# Debug_Board_-_Rev_A.net
KiCad netlist of a schematic drawn in EAGLE
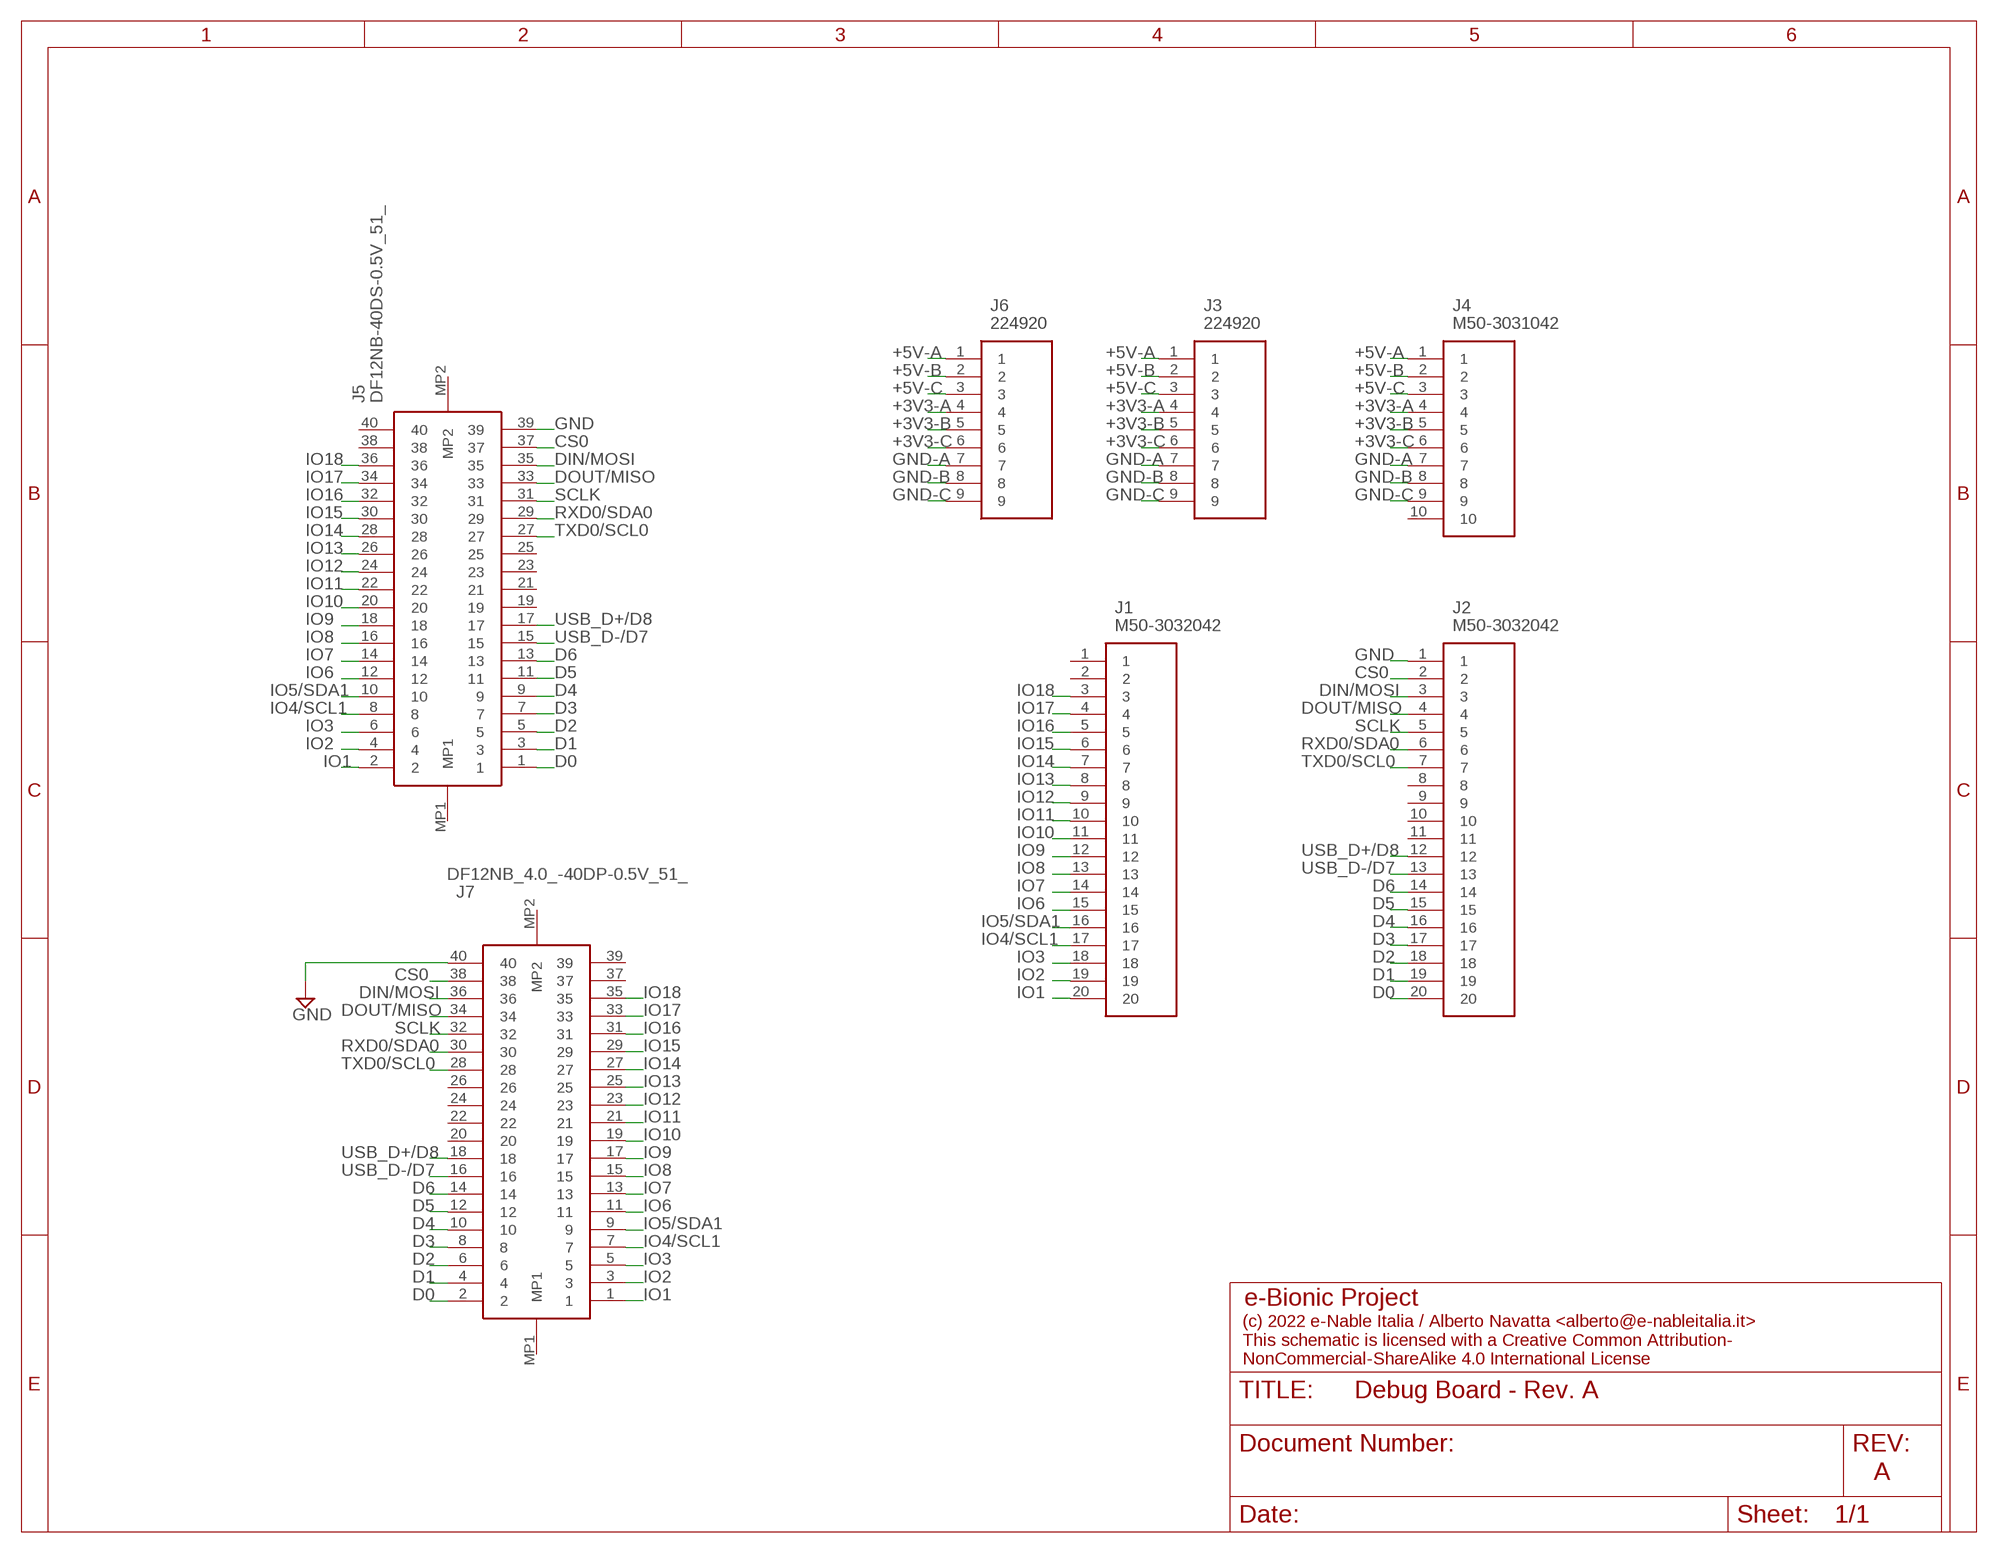
[diagram p0: schematic, sheet 1]

(export (version "E")
  (design (tool "Eeschema 10.0.6"))
  (components
    (comp (ref "J1")
      (value "M50-3032042")
      (footprint "eagle-import:M503032042")
      (fields (field (name "MOUSER_PART_NUMBER") "855-M50-3032042"))
      (libsource (lib "eagle-import") (part "M50-3032042"))
    )
    (comp (ref "J2")
      (value "M50-3032042")
      (footprint "eagle-import:M503032042")
      (fields (field (name "MOUSER_PART_NUMBER") "855-M50-3032042"))
      (libsource (lib "eagle-import") (part "M50-3032042"))
    )
    (comp (ref "J3")
      (value "224920")
      (footprint "eagle-import:224920")
      (fields (field (name "MOUSER_PART_NUMBER") "305-224920"))
      (libsource (lib "eagle-import") (part "224920"))
    )
    (comp (ref "J4")
      (value "M50-3031042")
      (footprint "eagle-import:M503031042")
      (fields (field (name "MOUSER_PART_NUMBER") "855-M50-3031042"))
      (libsource (lib "eagle-import") (part "M50-3031042"))
    )
    (comp (ref "J5")
      (value "DF12NB-40DS-0.5V_51_")
      (footprint "eagle-import:DF12NB40DS05V51")
      (fields
        (field (name "MANUFACTURER_PART_NUMBER") "DF12NB-40DS-0.5V(51)")
        (field (name "MOUSER_PART_NUMBER") "798-DF12NB40DS0551")
      )
      (libsource (lib "eagle-import") (part "DF12NB-40DS-0.5V_51_"))
    )
    (comp (ref "J6")
      (value "224920")
      (footprint "eagle-import:224920")
      (fields (field (name "MOUSER_PART_NUMBER") "305-224920"))
      (libsource (lib "eagle-import") (part "224920"))
    )
    (comp (ref "J7")
      (value "DF12NB_4.0_-40DP-0.5V_51_")
      (footprint "eagle-import:DF12NB4040DP05V51")
      (fields
        (field (name "MANUFACTURER_PART_NUMBER") "DF12NB(4.0)-40DP-0.5V(51)")
        (field (name "MOUSER_PART_NUMBER") "798-DF12NB4040DP0551")
      )
      (libsource (lib "eagle-import") (part "DF12NB_4.0_-40DP-0.5V_51_"))
    )
  )
  (nets
    (net (code "1") (name "/+3V3-A") (class "Default")
      (node (ref "J3") (pin "4") (pinfunction "4_4") (pintype "bidirectional"))
      (node (ref "J4") (pin "4") (pinfunction "4_4") (pintype "bidirectional"))
      (node (ref "J6") (pin "4") (pinfunction "4_4") (pintype "bidirectional"))
    )
    (net (code "2") (name "/+3V3-B") (class "Default")
      (node (ref "J3") (pin "5") (pinfunction "5_5") (pintype "bidirectional"))
      (node (ref "J4") (pin "5") (pinfunction "5_5") (pintype "bidirectional"))
      (node (ref "J6") (pin "5") (pinfunction "5_5") (pintype "bidirectional"))
    )
    (net (code "3") (name "/+3V3-C") (class "Default")
      (node (ref "J3") (pin "6") (pinfunction "6_6") (pintype "bidirectional"))
      (node (ref "J4") (pin "6") (pinfunction "6_6") (pintype "bidirectional"))
      (node (ref "J6") (pin "6") (pinfunction "6_6") (pintype "bidirectional"))
    )
    (net (code "4") (name "/+5V-A") (class "Default")
      (node (ref "J3") (pin "1") (pinfunction "1_1") (pintype "bidirectional"))
      (node (ref "J4") (pin "1") (pinfunction "1_1") (pintype "bidirectional"))
      (node (ref "J6") (pin "1") (pinfunction "1_1") (pintype "bidirectional"))
    )
    (net (code "5") (name "/+5V-B") (class "Default")
      (node (ref "J3") (pin "2") (pinfunction "2_2") (pintype "bidirectional"))
      (node (ref "J4") (pin "2") (pinfunction "2_2") (pintype "bidirectional"))
      (node (ref "J6") (pin "2") (pinfunction "2_2") (pintype "bidirectional"))
    )
    (net (code "6") (name "/+5V-C") (class "Default")
      (node (ref "J3") (pin "3") (pinfunction "3_3") (pintype "bidirectional"))
      (node (ref "J4") (pin "3") (pinfunction "3_3") (pintype "bidirectional"))
      (node (ref "J6") (pin "3") (pinfunction "3_3") (pintype "bidirectional"))
    )
    (net (code "7") (name "/CS0") (class "Default")
      (node (ref "J2") (pin "2") (pinfunction "2_2") (pintype "bidirectional"))
      (node (ref "J5") (pin "37") (pinfunction "37_37") (pintype "bidirectional"))
      (node (ref "J7") (pin "38") (pinfunction "38_38") (pintype "bidirectional"))
    )
    (net (code "8") (name "/D0") (class "Default")
      (node (ref "J2") (pin "20") (pinfunction "20_20") (pintype "bidirectional"))
      (node (ref "J5") (pin "1") (pinfunction "1_1") (pintype "bidirectional"))
      (node (ref "J7") (pin "2") (pinfunction "2_2") (pintype "bidirectional"))
    )
    (net (code "9") (name "/D1") (class "Default")
      (node (ref "J2") (pin "19") (pinfunction "19_19") (pintype "bidirectional"))
      (node (ref "J5") (pin "3") (pinfunction "3_3") (pintype "bidirectional"))
      (node (ref "J7") (pin "4") (pinfunction "4_4") (pintype "bidirectional"))
    )
    (net (code "10") (name "/D2") (class "Default")
      (node (ref "J2") (pin "18") (pinfunction "18_18") (pintype "bidirectional"))
      (node (ref "J5") (pin "5") (pinfunction "5_5") (pintype "bidirectional"))
      (node (ref "J7") (pin "6") (pinfunction "6_6") (pintype "bidirectional"))
    )
    (net (code "11") (name "/D3") (class "Default")
      (node (ref "J2") (pin "17") (pinfunction "17_17") (pintype "bidirectional"))
      (node (ref "J5") (pin "7") (pinfunction "7_7") (pintype "bidirectional"))
      (node (ref "J7") (pin "8") (pinfunction "8_8") (pintype "bidirectional"))
    )
    (net (code "12") (name "/D4") (class "Default")
      (node (ref "J2") (pin "16") (pinfunction "16_16") (pintype "bidirectional"))
      (node (ref "J5") (pin "9") (pinfunction "9_9") (pintype "bidirectional"))
      (node (ref "J7") (pin "10") (pinfunction "10_10") (pintype "bidirectional"))
    )
    (net (code "13") (name "/D5") (class "Default")
      (node (ref "J2") (pin "15") (pinfunction "15_15") (pintype "bidirectional"))
      (node (ref "J5") (pin "11") (pinfunction "11_11") (pintype "bidirectional"))
      (node (ref "J7") (pin "12") (pinfunction "12_12") (pintype "bidirectional"))
    )
    (net (code "14") (name "/D6") (class "Default")
      (node (ref "J2") (pin "14") (pinfunction "14_14") (pintype "bidirectional"))
      (node (ref "J5") (pin "13") (pinfunction "13_13") (pintype "bidirectional"))
      (node (ref "J7") (pin "14") (pinfunction "14_14") (pintype "bidirectional"))
    )
    (net (code "15") (name "/DIN{slash}MOSI") (class "Default")
      (node (ref "J2") (pin "3") (pinfunction "3_3") (pintype "bidirectional"))
      (node (ref "J5") (pin "35") (pinfunction "35_35") (pintype "bidirectional"))
      (node (ref "J7") (pin "36") (pinfunction "36_36") (pintype "bidirectional"))
    )
    (net (code "16") (name "/DOUT{slash}MISO") (class "Default")
      (node (ref "J2") (pin "4") (pinfunction "4_4") (pintype "bidirectional"))
      (node (ref "J5") (pin "33") (pinfunction "33_33") (pintype "bidirectional"))
      (node (ref "J7") (pin "34") (pinfunction "34_34") (pintype "bidirectional"))
    )
    (net (code "17") (name "/GND-A") (class "Default")
      (node (ref "J3") (pin "7") (pinfunction "7_7") (pintype "bidirectional"))
      (node (ref "J4") (pin "7") (pinfunction "7_7") (pintype "bidirectional"))
      (node (ref "J6") (pin "7") (pinfunction "7_7") (pintype "bidirectional"))
    )
    (net (code "18") (name "/GND-B") (class "Default")
      (node (ref "J3") (pin "8") (pinfunction "8_8") (pintype "bidirectional"))
      (node (ref "J4") (pin "8") (pinfunction "8_8") (pintype "bidirectional"))
      (node (ref "J6") (pin "8") (pinfunction "8_8") (pintype "bidirectional"))
    )
    (net (code "19") (name "/GND-C") (class "Default")
      (node (ref "J3") (pin "9") (pinfunction "9_9") (pintype "bidirectional"))
      (node (ref "J4") (pin "9") (pinfunction "9_9") (pintype "bidirectional"))
      (node (ref "J6") (pin "9") (pinfunction "9_9") (pintype "bidirectional"))
    )
    (net (code "20") (name "/IO1") (class "Default")
      (node (ref "J1") (pin "20") (pinfunction "20_20") (pintype "bidirectional"))
      (node (ref "J5") (pin "2") (pinfunction "2_2") (pintype "bidirectional"))
      (node (ref "J7") (pin "1") (pinfunction "1_1") (pintype "bidirectional"))
    )
    (net (code "21") (name "/IO2") (class "Default")
      (node (ref "J1") (pin "19") (pinfunction "19_19") (pintype "bidirectional"))
      (node (ref "J5") (pin "4") (pinfunction "4_4") (pintype "bidirectional"))
      (node (ref "J7") (pin "3") (pinfunction "3_3") (pintype "bidirectional"))
    )
    (net (code "22") (name "/IO3") (class "Default")
      (node (ref "J1") (pin "18") (pinfunction "18_18") (pintype "bidirectional"))
      (node (ref "J5") (pin "6") (pinfunction "6_6") (pintype "bidirectional"))
      (node (ref "J7") (pin "5") (pinfunction "5_5") (pintype "bidirectional"))
    )
    (net (code "23") (name "/IO4{slash}SCL1") (class "Default")
      (node (ref "J1") (pin "17") (pinfunction "17_17") (pintype "bidirectional"))
      (node (ref "J5") (pin "8") (pinfunction "8_8") (pintype "bidirectional"))
      (node (ref "J7") (pin "7") (pinfunction "7_7") (pintype "bidirectional"))
    )
    (net (code "24") (name "/IO5{slash}SDA1") (class "Default")
      (node (ref "J1") (pin "16") (pinfunction "16_16") (pintype "bidirectional"))
      (node (ref "J5") (pin "10") (pinfunction "10_10") (pintype "bidirectional"))
      (node (ref "J7") (pin "9") (pinfunction "9_9") (pintype "bidirectional"))
    )
    (net (code "25") (name "/IO6") (class "Default")
      (node (ref "J1") (pin "15") (pinfunction "15_15") (pintype "bidirectional"))
      (node (ref "J5") (pin "12") (pinfunction "12_12") (pintype "bidirectional"))
      (node (ref "J7") (pin "11") (pinfunction "11_11") (pintype "bidirectional"))
    )
    (net (code "26") (name "/IO7") (class "Default")
      (node (ref "J1") (pin "14") (pinfunction "14_14") (pintype "bidirectional"))
      (node (ref "J5") (pin "14") (pinfunction "14_14") (pintype "bidirectional"))
      (node (ref "J7") (pin "13") (pinfunction "13_13") (pintype "bidirectional"))
    )
    (net (code "27") (name "/IO8") (class "Default")
      (node (ref "J1") (pin "13") (pinfunction "13_13") (pintype "bidirectional"))
      (node (ref "J5") (pin "16") (pinfunction "16_16") (pintype "bidirectional"))
      (node (ref "J7") (pin "15") (pinfunction "15_15") (pintype "bidirectional"))
    )
    (net (code "28") (name "/IO9") (class "Default")
      (node (ref "J1") (pin "12") (pinfunction "12_12") (pintype "bidirectional"))
      (node (ref "J5") (pin "18") (pinfunction "18_18") (pintype "bidirectional"))
      (node (ref "J7") (pin "17") (pinfunction "17_17") (pintype "bidirectional"))
    )
    (net (code "29") (name "/IO10") (class "Default")
      (node (ref "J1") (pin "11") (pinfunction "11_11") (pintype "bidirectional"))
      (node (ref "J5") (pin "20") (pinfunction "20_20") (pintype "bidirectional"))
      (node (ref "J7") (pin "19") (pinfunction "19_19") (pintype "bidirectional"))
    )
    (net (code "30") (name "/IO11") (class "Default")
      (node (ref "J1") (pin "10") (pinfunction "10_10") (pintype "bidirectional"))
      (node (ref "J5") (pin "22") (pinfunction "22_22") (pintype "bidirectional"))
      (node (ref "J7") (pin "21") (pinfunction "21_21") (pintype "bidirectional"))
    )
    (net (code "31") (name "/IO12") (class "Default")
      (node (ref "J1") (pin "9") (pinfunction "9_9") (pintype "bidirectional"))
      (node (ref "J5") (pin "24") (pinfunction "24_24") (pintype "bidirectional"))
      (node (ref "J7") (pin "23") (pinfunction "23_23") (pintype "bidirectional"))
    )
    (net (code "32") (name "/IO13") (class "Default")
      (node (ref "J1") (pin "8") (pinfunction "8_8") (pintype "bidirectional"))
      (node (ref "J5") (pin "26") (pinfunction "26_26") (pintype "bidirectional"))
      (node (ref "J7") (pin "25") (pinfunction "25_25") (pintype "bidirectional"))
    )
    (net (code "33") (name "/IO14") (class "Default")
      (node (ref "J1") (pin "7") (pinfunction "7_7") (pintype "bidirectional"))
      (node (ref "J5") (pin "28") (pinfunction "28_28") (pintype "bidirectional"))
      (node (ref "J7") (pin "27") (pinfunction "27_27") (pintype "bidirectional"))
    )
    (net (code "34") (name "/IO15") (class "Default")
      (node (ref "J1") (pin "6") (pinfunction "6_6") (pintype "bidirectional"))
      (node (ref "J5") (pin "30") (pinfunction "30_30") (pintype "bidirectional"))
      (node (ref "J7") (pin "29") (pinfunction "29_29") (pintype "bidirectional"))
    )
    (net (code "35") (name "/IO16") (class "Default")
      (node (ref "J1") (pin "5") (pinfunction "5_5") (pintype "bidirectional"))
      (node (ref "J5") (pin "32") (pinfunction "32_32") (pintype "bidirectional"))
      (node (ref "J7") (pin "31") (pinfunction "31_31") (pintype "bidirectional"))
    )
    (net (code "36") (name "/IO17") (class "Default")
      (node (ref "J1") (pin "4") (pinfunction "4_4") (pintype "bidirectional"))
      (node (ref "J5") (pin "34") (pinfunction "34_34") (pintype "bidirectional"))
      (node (ref "J7") (pin "33") (pinfunction "33_33") (pintype "bidirectional"))
    )
    (net (code "37") (name "/IO18") (class "Default")
      (node (ref "J1") (pin "3") (pinfunction "3_3") (pintype "bidirectional"))
      (node (ref "J5") (pin "36") (pinfunction "36_36") (pintype "bidirectional"))
      (node (ref "J7") (pin "35") (pinfunction "35_35") (pintype "bidirectional"))
    )
    (net (code "38") (name "/RXD0{slash}SDA0") (class "Default")
      (node (ref "J2") (pin "6") (pinfunction "6_6") (pintype "bidirectional"))
      (node (ref "J5") (pin "29") (pinfunction "29_29") (pintype "bidirectional"))
      (node (ref "J7") (pin "30") (pinfunction "30_30") (pintype "bidirectional"))
    )
    (net (code "39") (name "/SCLK") (class "Default")
      (node (ref "J2") (pin "5") (pinfunction "5_5") (pintype "bidirectional"))
      (node (ref "J5") (pin "31") (pinfunction "31_31") (pintype "bidirectional"))
      (node (ref "J7") (pin "32") (pinfunction "32_32") (pintype "bidirectional"))
    )
    (net (code "40") (name "/TXD0{slash}SCL0") (class "Default")
      (node (ref "J2") (pin "7") (pinfunction "7_7") (pintype "bidirectional"))
      (node (ref "J5") (pin "27") (pinfunction "27_27") (pintype "bidirectional"))
      (node (ref "J7") (pin "28") (pinfunction "28_28") (pintype "bidirectional"))
    )
    (net (code "41") (name "/USB_D+{slash}D8") (class "Default")
      (node (ref "J2") (pin "12") (pinfunction "12_12") (pintype "bidirectional"))
      (node (ref "J5") (pin "17") (pinfunction "17_17") (pintype "bidirectional"))
      (node (ref "J7") (pin "18") (pinfunction "18_18") (pintype "bidirectional"))
    )
    (net (code "42") (name "/USB_D-{slash}D7") (class "Default")
      (node (ref "J2") (pin "13") (pinfunction "13_13") (pintype "bidirectional"))
      (node (ref "J5") (pin "15") (pinfunction "15_15") (pintype "bidirectional"))
      (node (ref "J7") (pin "16") (pinfunction "16_16") (pintype "bidirectional"))
    )
    (net (code "43") (name "GND") (class "Default")
      (node (ref "J2") (pin "1") (pinfunction "1_1") (pintype "bidirectional"))
      (node (ref "J5") (pin "39") (pinfunction "39_39") (pintype "bidirectional"))
      (node (ref "J7") (pin "40") (pinfunction "40_40") (pintype "bidirectional"))
    )
    (net (code "44") (name "unconnected-(J1-Pad1)") (class "Default")
      (node (ref "J1") (pin "1") (pinfunction "1_1") (pintype "bidirectional"))
    )
    (net (code "45") (name "unconnected-(J1-Pad2)") (class "Default")
      (node (ref "J1") (pin "2") (pinfunction "2_2") (pintype "bidirectional"))
    )
    (net (code "46") (name "unconnected-(J2-Pad8)") (class "Default")
      (node (ref "J2") (pin "8") (pinfunction "8_8") (pintype "bidirectional"))
    )
    (net (code "47") (name "unconnected-(J2-Pad9)") (class "Default")
      (node (ref "J2") (pin "9") (pinfunction "9_9") (pintype "bidirectional"))
    )
    (net (code "48") (name "unconnected-(J2-Pad10)") (class "Default")
      (node (ref "J2") (pin "10") (pinfunction "10_10") (pintype "bidirectional"))
    )
    (net (code "49") (name "unconnected-(J2-Pad11)") (class "Default")
      (node (ref "J2") (pin "11") (pinfunction "11_11") (pintype "bidirectional"))
    )
    (net (code "50") (name "unconnected-(J4-Pad10)") (class "Default")
      (node (ref "J4") (pin "10") (pinfunction "10_10") (pintype "bidirectional"))
    )
    (net (code "51") (name "unconnected-(J5-Pad19)") (class "Default")
      (node (ref "J5") (pin "19") (pinfunction "19_19") (pintype "bidirectional"))
    )
    (net (code "52") (name "unconnected-(J5-Pad21)") (class "Default")
      (node (ref "J5") (pin "21") (pinfunction "21_21") (pintype "bidirectional"))
    )
    (net (code "53") (name "unconnected-(J5-Pad23)") (class "Default")
      (node (ref "J5") (pin "23") (pinfunction "23_23") (pintype "bidirectional"))
    )
    (net (code "54") (name "unconnected-(J5-Pad25)") (class "Default")
      (node (ref "J5") (pin "25") (pinfunction "25_25") (pintype "bidirectional"))
    )
    (net (code "55") (name "unconnected-(J5-Pad38)") (class "Default")
      (node (ref "J5") (pin "38") (pinfunction "38_38") (pintype "bidirectional"))
    )
    (net (code "56") (name "unconnected-(J5-Pad40)") (class "Default")
      (node (ref "J5") (pin "40") (pinfunction "40_40") (pintype "bidirectional"))
    )
    (net (code "57") (name "unconnected-(J5-PadMP1)") (class "Default")
      (node (ref "J5") (pin "MP1") (pinfunction "MP1_MP1") (pintype "bidirectional"))
    )
    (net (code "58") (name "unconnected-(J5-PadMP2)") (class "Default")
      (node (ref "J5") (pin "MP2") (pinfunction "MP2_MP2") (pintype "bidirectional"))
    )
    (net (code "59") (name "unconnected-(J7-Pad20)") (class "Default")
      (node (ref "J7") (pin "20") (pinfunction "20_20") (pintype "bidirectional"))
    )
    (net (code "60") (name "unconnected-(J7-Pad22)") (class "Default")
      (node (ref "J7") (pin "22") (pinfunction "22_22") (pintype "bidirectional"))
    )
    (net (code "61") (name "unconnected-(J7-Pad24)") (class "Default")
      (node (ref "J7") (pin "24") (pinfunction "24_24") (pintype "bidirectional"))
    )
    (net (code "62") (name "unconnected-(J7-Pad26)") (class "Default")
      (node (ref "J7") (pin "26") (pinfunction "26_26") (pintype "bidirectional"))
    )
    (net (code "63") (name "unconnected-(J7-Pad37)") (class "Default")
      (node (ref "J7") (pin "37") (pinfunction "37_37") (pintype "bidirectional"))
    )
    (net (code "64") (name "unconnected-(J7-Pad39)") (class "Default")
      (node (ref "J7") (pin "39") (pinfunction "39_39") (pintype "bidirectional"))
    )
    (net (code "65") (name "unconnected-(J7-PadMP1)") (class "Default")
      (node (ref "J7") (pin "MP1") (pinfunction "MP1_MP1") (pintype "bidirectional"))
    )
    (net (code "66") (name "unconnected-(J7-PadMP2)") (class "Default")
      (node (ref "J7") (pin "MP2") (pinfunction "MP2_MP2") (pintype "bidirectional"))
    )
  )
)
